# mixer.net
KiCad netlist of a schematic drawn in EAGLE
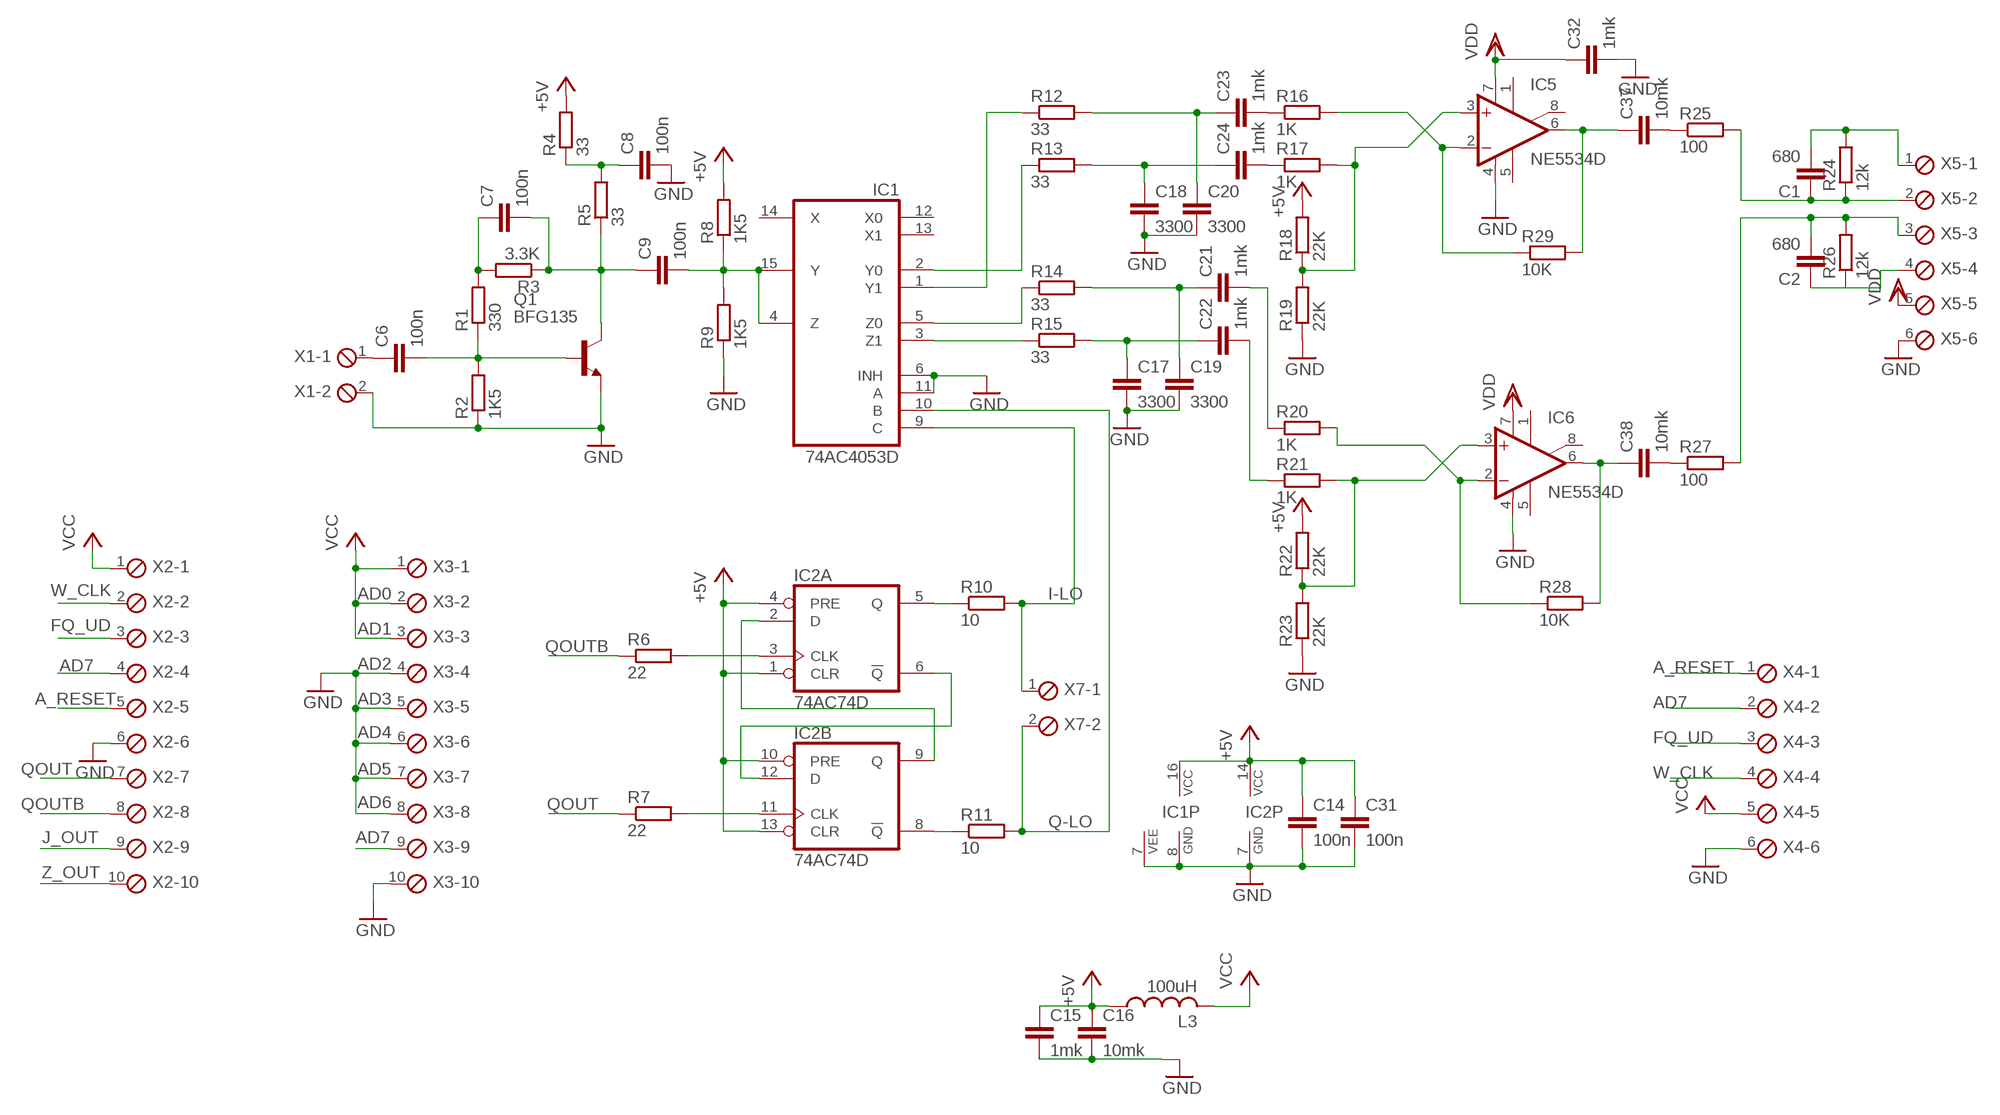
[diagram p0: schematic, sheet 1]

(export (version "E")
  (design (tool "Eeschema 10.0.6"))
  (components
    (comp (ref "C1")
      (value "680")
      (footprint "eagle-import:C0805")
      (libsource (lib "eagle-import") (part "C-EUC0805"))
    )
    (comp (ref "C2")
      (value "680")
      (footprint "eagle-import:C0805")
      (libsource (lib "eagle-import") (part "C-EUC0805"))
    )
    (comp (ref "C6")
      (value "100n")
      (footprint "eagle-import:C0603")
      (libsource (lib "eagle-import") (part "C-EUC0603"))
    )
    (comp (ref "C7")
      (value "100n")
      (footprint "eagle-import:C0603")
      (libsource (lib "eagle-import") (part "C-EUC0603"))
    )
    (comp (ref "C8")
      (value "100n")
      (footprint "eagle-import:C0603")
      (libsource (lib "eagle-import") (part "C-EUC0603"))
    )
    (comp (ref "C9")
      (value "100n")
      (footprint "eagle-import:C0603")
      (libsource (lib "eagle-import") (part "C-EUC0603"))
    )
    (comp (ref "C14")
      (value "100n")
      (footprint "eagle-import:C0603")
      (libsource (lib "eagle-import") (part "C-EUC0603"))
    )
    (comp (ref "C15")
      (value "1mk")
      (footprint "eagle-import:C0603")
      (libsource (lib "eagle-import") (part "C-EUC0603"))
    )
    (comp (ref "C16")
      (value "10mk")
      (footprint "eagle-import:C0805")
      (libsource (lib "eagle-import") (part "C-EUC0805"))
    )
    (comp (ref "C17")
      (value "3300")
      (footprint "eagle-import:C0805")
      (libsource (lib "eagle-import") (part "C-EUC0805"))
    )
    (comp (ref "C18")
      (value "3300")
      (footprint "eagle-import:C0805")
      (libsource (lib "eagle-import") (part "C-EUC0805"))
    )
    (comp (ref "C19")
      (value "3300")
      (footprint "eagle-import:C0805")
      (libsource (lib "eagle-import") (part "C-EUC0805"))
    )
    (comp (ref "C20")
      (value "3300")
      (footprint "eagle-import:C0805")
      (libsource (lib "eagle-import") (part "C-EUC0805"))
    )
    (comp (ref "C21")
      (value "1mk")
      (footprint "eagle-import:C0603")
      (libsource (lib "eagle-import") (part "C-EUC0603"))
    )
    (comp (ref "C22")
      (value "1mk")
      (footprint "eagle-import:C0603")
      (libsource (lib "eagle-import") (part "C-EUC0603"))
    )
    (comp (ref "C23")
      (value "1mk")
      (footprint "eagle-import:C0603")
      (libsource (lib "eagle-import") (part "C-EUC0603"))
    )
    (comp (ref "C24")
      (value "1mk")
      (footprint "eagle-import:C0603")
      (libsource (lib "eagle-import") (part "C-EUC0603"))
    )
    (comp (ref "C31")
      (value "100n")
      (footprint "eagle-import:C0603")
      (libsource (lib "eagle-import") (part "C-EUC0603"))
    )
    (comp (ref "C32")
      (value "1mk")
      (footprint "eagle-import:C0603")
      (libsource (lib "eagle-import") (part "C-EUC0603"))
    )
    (comp (ref "C37")
      (value "10mk")
      (footprint "eagle-import:C0805")
      (libsource (lib "eagle-import") (part "C-EUC0805"))
    )
    (comp (ref "C38")
      (value "10mk")
      (footprint "eagle-import:C0805")
      (libsource (lib "eagle-import") (part "C-EUC0805"))
    )
    (comp (ref "IC1")
      (value "74AC4053D")
      (footprint "eagle-import:SO16")
      (libsource (lib "eagle-import") (part "4053D"))
    )
    (comp (ref "IC2")
      (value "74AC74D")
      (footprint "eagle-import:SO14")
      (libsource (lib "eagle-import") (part "7474DAC"))
    )
    (comp (ref "IC5")
      (value "NE5534D")
      (footprint "eagle-import:SO08")
      (libsource (lib "eagle-import") (part "NE5534D"))
    )
    (comp (ref "IC6")
      (value "NE5534D")
      (footprint "eagle-import:SO08")
      (libsource (lib "eagle-import") (part "NE5534D"))
    )
    (comp (ref "L3")
      (value "100uH")
      (footprint "eagle-import:0207_12")
      (libsource (lib "eagle-import") (part "L-US0207/12"))
    )
    (comp (ref "Q1")
      (value "BFG135")
      (footprint "eagle-import:SOT223")
      (libsource (lib "eagle-import") (part "BFG135"))
    )
    (comp (ref "R1")
      (value "330")
      (footprint "eagle-import:R0603")
      (libsource (lib "eagle-import") (part "R-EU_R0603"))
    )
    (comp (ref "R2")
      (value "1K5")
      (footprint "eagle-import:R0603")
      (libsource (lib "eagle-import") (part "R-EU_R0603"))
    )
    (comp (ref "R3")
      (value "3.3K")
      (footprint "eagle-import:R0603")
      (libsource (lib "eagle-import") (part "R-EU_R0603"))
    )
    (comp (ref "R4")
      (value "33")
      (footprint "eagle-import:R0603")
      (libsource (lib "eagle-import") (part "R-EU_R0603"))
    )
    (comp (ref "R5")
      (value "33")
      (footprint "eagle-import:R0603")
      (libsource (lib "eagle-import") (part "R-EU_R0603"))
    )
    (comp (ref "R6")
      (value "22")
      (footprint "eagle-import:R0603")
      (libsource (lib "eagle-import") (part "R-EU_R0603"))
    )
    (comp (ref "R7")
      (value "22")
      (footprint "eagle-import:R0603")
      (libsource (lib "eagle-import") (part "R-EU_R0603"))
    )
    (comp (ref "R8")
      (value "1K5")
      (footprint "eagle-import:R0603")
      (libsource (lib "eagle-import") (part "R-EU_R0603"))
    )
    (comp (ref "R9")
      (value "1K5")
      (footprint "eagle-import:R0603")
      (libsource (lib "eagle-import") (part "R-EU_R0603"))
    )
    (comp (ref "R10")
      (value "10")
      (footprint "eagle-import:R0603")
      (libsource (lib "eagle-import") (part "R-EU_R0603"))
    )
    (comp (ref "R11")
      (value "10")
      (footprint "eagle-import:R0603")
      (libsource (lib "eagle-import") (part "R-EU_R0603"))
    )
    (comp (ref "R12")
      (value "33")
      (footprint "eagle-import:R0603")
      (libsource (lib "eagle-import") (part "R-EU_R0603"))
    )
    (comp (ref "R13")
      (value "33")
      (footprint "eagle-import:R0603")
      (libsource (lib "eagle-import") (part "R-EU_R0603"))
    )
    (comp (ref "R14")
      (value "33")
      (footprint "eagle-import:R0603")
      (libsource (lib "eagle-import") (part "R-EU_R0603"))
    )
    (comp (ref "R15")
      (value "33")
      (footprint "eagle-import:R0603")
      (libsource (lib "eagle-import") (part "R-EU_R0603"))
    )
    (comp (ref "R16")
      (value "1K")
      (footprint "eagle-import:R0603")
      (libsource (lib "eagle-import") (part "R-EU_R0603"))
    )
    (comp (ref "R17")
      (value "1K")
      (footprint "eagle-import:R0603")
      (libsource (lib "eagle-import") (part "R-EU_R0603"))
    )
    (comp (ref "R18")
      (value "22K")
      (footprint "eagle-import:R0603")
      (libsource (lib "eagle-import") (part "R-EU_R0603"))
    )
    (comp (ref "R19")
      (value "22K")
      (footprint "eagle-import:R0603")
      (libsource (lib "eagle-import") (part "R-EU_R0603"))
    )
    (comp (ref "R20")
      (value "1K")
      (footprint "eagle-import:R0603")
      (libsource (lib "eagle-import") (part "R-EU_R0603"))
    )
    (comp (ref "R21")
      (value "1K")
      (footprint "eagle-import:R0603")
      (libsource (lib "eagle-import") (part "R-EU_R0603"))
    )
    (comp (ref "R22")
      (value "22K")
      (footprint "eagle-import:R0603")
      (libsource (lib "eagle-import") (part "R-EU_R0603"))
    )
    (comp (ref "R23")
      (value "22K")
      (footprint "eagle-import:R0603")
      (libsource (lib "eagle-import") (part "R-EU_R0603"))
    )
    (comp (ref "R24")
      (value "12k")
      (footprint "eagle-import:R0603")
      (libsource (lib "eagle-import") (part "R-EU_R0603"))
    )
    (comp (ref "R25")
      (value "100")
      (footprint "eagle-import:R0603")
      (libsource (lib "eagle-import") (part "R-EU_R0603"))
    )
    (comp (ref "R26")
      (value "12k")
      (footprint "eagle-import:R0603")
      (libsource (lib "eagle-import") (part "R-EU_R0603"))
    )
    (comp (ref "R27")
      (value "100")
      (footprint "eagle-import:R0603")
      (libsource (lib "eagle-import") (part "R-EU_R0603"))
    )
    (comp (ref "R28")
      (value "10K")
      (footprint "eagle-import:R0603")
      (libsource (lib "eagle-import") (part "R-EU_R0603"))
    )
    (comp (ref "R29")
      (value "10K")
      (footprint "eagle-import:R0603")
      (libsource (lib "eagle-import") (part "R-EU_R0603"))
    )
    (comp (ref "X1")
      (value "MPT2")
      (footprint "eagle-import:2POL254")
      (libsource (lib "eagle-import") (part "MPT2"))
    )
    (comp (ref "X2")
      (value "MPT10")
      (footprint "eagle-import:10POL254")
      (libsource (lib "eagle-import") (part "MPT10"))
    )
    (comp (ref "X3")
      (value "MPT10")
      (footprint "eagle-import:10POL254")
      (libsource (lib "eagle-import") (part "MPT10"))
    )
    (comp (ref "X4")
      (value "MPT6")
      (footprint "eagle-import:6POL254")
      (libsource (lib "eagle-import") (part "MPT6"))
    )
    (comp (ref "X5")
      (value "MPT6")
      (footprint "eagle-import:6POL254")
      (libsource (lib "eagle-import") (part "MPT6"))
    )
    (comp (ref "X7")
      (value "MPT2")
      (footprint "eagle-import:2POL254")
      (libsource (lib "eagle-import") (part "MPT2"))
    )
  )
  (nets
    (net (code "1") (name "+5V") (class "Default")
      (node (ref "C14") (pin "1") (pinfunction "1_1") (pintype "passive"))
      (node (ref "C15") (pin "1") (pinfunction "1_1") (pintype "passive"))
      (node (ref "C16") (pin "1") (pinfunction "1_1") (pintype "passive"))
      (node (ref "C31") (pin "1") (pinfunction "1_1") (pintype "passive"))
      (node (ref "IC1") (pin "16") (pinfunction "VCC_16") (pintype "power_in"))
      (node (ref "IC2") (pin "1") (pinfunction "CLR_1") (pintype "input"))
      (node (ref "IC2") (pin "10") (pinfunction "PRE_10") (pintype "input"))
      (node (ref "IC2") (pin "13") (pinfunction "CLR_13") (pintype "input"))
      (node (ref "IC2") (pin "14") (pinfunction "VCC_14") (pintype "power_in"))
      (node (ref "IC2") (pin "4") (pinfunction "PRE_4") (pintype "input"))
      (node (ref "L3") (pin "1") (pinfunction "1_1") (pintype "passive"))
      (node (ref "R18") (pin "2") (pinfunction "2_2") (pintype "passive"))
      (node (ref "R22") (pin "2") (pinfunction "2_2") (pintype "passive"))
      (node (ref "R4") (pin "2") (pinfunction "2_2") (pintype "passive"))
      (node (ref "R8") (pin "2") (pinfunction "2_2") (pintype "passive"))
    )
    (net (code "2") (name "/AD7") (class "Default")
      (node (ref "X2") (pin "4") (pinfunction "1_4") (pintype "passive"))
      (node (ref "X4") (pin "2") (pinfunction "1_2") (pintype "passive"))
    )
    (net (code "3") (name "/A_RESET") (class "Default")
      (node (ref "X2") (pin "5") (pinfunction "1_5") (pintype "passive"))
      (node (ref "X4") (pin "1") (pinfunction "1_1") (pintype "passive"))
    )
    (net (code "4") (name "/FQ_UD") (class "Default")
      (node (ref "X2") (pin "3") (pinfunction "1_3") (pintype "passive"))
      (node (ref "X4") (pin "3") (pinfunction "1_3") (pintype "passive"))
    )
    (net (code "5") (name "/I-LO") (class "Default")
      (node (ref "IC1") (pin "9") (pinfunction "C_9") (pintype "input"))
      (node (ref "R10") (pin "2") (pinfunction "2_2") (pintype "passive"))
      (node (ref "X7") (pin "1") (pinfunction "1_1") (pintype "passive"))
    )
    (net (code "6") (name "/J_OUT") (class "Default")
      (node (ref "X2") (pin "9") (pinfunction "1_9") (pintype "passive"))
    )
    (net (code "7") (name "/Q-LO") (class "Default")
      (node (ref "IC1") (pin "10") (pinfunction "B_10") (pintype "input"))
      (node (ref "R11") (pin "2") (pinfunction "2_2") (pintype "passive"))
      (node (ref "X7") (pin "2") (pinfunction "1_2") (pintype "passive"))
    )
    (net (code "8") (name "/QOUT") (class "Default")
      (node (ref "R7") (pin "1") (pinfunction "1_1") (pintype "passive"))
      (node (ref "X2") (pin "7") (pinfunction "1_7") (pintype "passive"))
    )
    (net (code "9") (name "/QOUTB") (class "Default")
      (node (ref "R6") (pin "1") (pinfunction "1_1") (pintype "passive"))
      (node (ref "X2") (pin "8") (pinfunction "1_8") (pintype "passive"))
    )
    (net (code "10") (name "/W_CLK") (class "Default")
      (node (ref "X2") (pin "2") (pinfunction "1_2") (pintype "passive"))
      (node (ref "X4") (pin "4") (pinfunction "1_4") (pintype "passive"))
    )
    (net (code "11") (name "/Z_OUT") (class "Default")
      (node (ref "X2") (pin "10") (pinfunction "1_10") (pintype "passive"))
    )
    (net (code "12") (name "GND") (class "Default")
      (node (ref "C14") (pin "2") (pinfunction "2_2") (pintype "passive"))
      (node (ref "C15") (pin "2") (pinfunction "2_2") (pintype "passive"))
      (node (ref "C16") (pin "2") (pinfunction "2_2") (pintype "passive"))
      (node (ref "C17") (pin "2") (pinfunction "2_2") (pintype "passive"))
      (node (ref "C18") (pin "2") (pinfunction "2_2") (pintype "passive"))
      (node (ref "C19") (pin "2") (pinfunction "2_2") (pintype "passive"))
      (node (ref "C20") (pin "2") (pinfunction "2_2") (pintype "passive"))
      (node (ref "C31") (pin "2") (pinfunction "2_2") (pintype "passive"))
      (node (ref "C32") (pin "2") (pinfunction "2_2") (pintype "passive"))
      (node (ref "C8") (pin "2") (pinfunction "2_2") (pintype "passive"))
      (node (ref "IC1") (pin "11") (pinfunction "A_11") (pintype "input"))
      (node (ref "IC1") (pin "6") (pinfunction "INH_6") (pintype "input"))
      (node (ref "IC1") (pin "7") (pinfunction "VEE_7") (pintype "power_in"))
      (node (ref "IC1") (pin "8") (pinfunction "GND_8") (pintype "power_in"))
      (node (ref "IC2") (pin "7") (pinfunction "GND_7") (pintype "power_in"))
      (node (ref "IC5") (pin "4") (pinfunction "V-_4") (pintype "power_in"))
      (node (ref "IC6") (pin "4") (pinfunction "V-_4") (pintype "power_in"))
      (node (ref "Q1") (pin "1") (pinfunction "E_1") (pintype "passive"))
      (node (ref "Q1") (pin "3") (pinfunction "E_3") (pintype "passive"))
      (node (ref "R19") (pin "1") (pinfunction "1_1") (pintype "passive"))
      (node (ref "R2") (pin "1") (pinfunction "1_1") (pintype "passive"))
      (node (ref "R23") (pin "1") (pinfunction "1_1") (pintype "passive"))
      (node (ref "R9") (pin "1") (pinfunction "1_1") (pintype "passive"))
      (node (ref "X1") (pin "2") (pinfunction "1_2") (pintype "passive"))
      (node (ref "X2") (pin "6") (pinfunction "1_6") (pintype "passive"))
      (node (ref "X3") (pin "10") (pinfunction "1_10") (pintype "passive"))
      (node (ref "X3") (pin "4") (pinfunction "1_4") (pintype "passive"))
      (node (ref "X3") (pin "5") (pinfunction "1_5") (pintype "passive"))
      (node (ref "X3") (pin "6") (pinfunction "1_6") (pintype "passive"))
      (node (ref "X3") (pin "7") (pinfunction "1_7") (pintype "passive"))
      (node (ref "X3") (pin "8") (pinfunction "1_8") (pintype "passive"))
      (node (ref "X4") (pin "6") (pinfunction "1_6") (pintype "passive"))
      (node (ref "X5") (pin "6") (pinfunction "1_6") (pintype "passive"))
    )
    (net (code "13") (name "Net-(C1-Pad2)") (class "Default")
      (node (ref "C1") (pin "2") (pinfunction "2_2") (pintype "passive"))
      (node (ref "R24") (pin "2") (pinfunction "2_2") (pintype "passive"))
      (node (ref "X5") (pin "1") (pinfunction "1_1") (pintype "passive"))
    )
    (net (code "14") (name "Net-(C6-Pad1)") (class "Default")
      (node (ref "C6") (pin "1") (pinfunction "1_1") (pintype "passive"))
      (node (ref "X1") (pin "1") (pinfunction "1_1") (pintype "passive"))
    )
    (net (code "15") (name "Net-(C7-Pad1)") (class "Default")
      (node (ref "C7") (pin "1") (pinfunction "1_1") (pintype "passive"))
      (node (ref "R1") (pin "2") (pinfunction "2_2") (pintype "passive"))
      (node (ref "R3") (pin "2") (pinfunction "2_2") (pintype "passive"))
    )
    (net (code "16") (name "Net-(C8-Pad1)") (class "Default")
      (node (ref "C8") (pin "1") (pinfunction "1_1") (pintype "passive"))
      (node (ref "R4") (pin "1") (pinfunction "1_1") (pintype "passive"))
      (node (ref "R5") (pin "2") (pinfunction "2_2") (pintype "passive"))
    )
    (net (code "17") (name "Net-(C17-Pad1)") (class "Default")
      (node (ref "C17") (pin "1") (pinfunction "1_1") (pintype "passive"))
      (node (ref "C22") (pin "1") (pinfunction "1_1") (pintype "passive"))
      (node (ref "R15") (pin "2") (pinfunction "2_2") (pintype "passive"))
    )
    (net (code "18") (name "Net-(C18-Pad1)") (class "Default")
      (node (ref "C18") (pin "1") (pinfunction "1_1") (pintype "passive"))
      (node (ref "C24") (pin "1") (pinfunction "1_1") (pintype "passive"))
      (node (ref "R13") (pin "2") (pinfunction "2_2") (pintype "passive"))
    )
    (net (code "19") (name "Net-(C19-Pad1)") (class "Default")
      (node (ref "C19") (pin "1") (pinfunction "1_1") (pintype "passive"))
      (node (ref "C21") (pin "1") (pinfunction "1_1") (pintype "passive"))
      (node (ref "R14") (pin "2") (pinfunction "2_2") (pintype "passive"))
    )
    (net (code "20") (name "Net-(C20-Pad1)") (class "Default")
      (node (ref "C20") (pin "1") (pinfunction "1_1") (pintype "passive"))
      (node (ref "C23") (pin "1") (pinfunction "1_1") (pintype "passive"))
      (node (ref "R12") (pin "2") (pinfunction "2_2") (pintype "passive"))
    )
    (net (code "21") (name "Net-(C21-Pad2)") (class "Default")
      (node (ref "C21") (pin "2") (pinfunction "2_2") (pintype "passive"))
      (node (ref "R20") (pin "1") (pinfunction "1_1") (pintype "passive"))
    )
    (net (code "22") (name "Net-(C22-Pad2)") (class "Default")
      (node (ref "C22") (pin "2") (pinfunction "2_2") (pintype "passive"))
      (node (ref "R21") (pin "1") (pinfunction "1_1") (pintype "passive"))
    )
    (net (code "23") (name "Net-(C23-Pad2)") (class "Default")
      (node (ref "C23") (pin "2") (pinfunction "2_2") (pintype "passive"))
      (node (ref "R16") (pin "1") (pinfunction "1_1") (pintype "passive"))
    )
    (net (code "24") (name "Net-(C24-Pad2)") (class "Default")
      (node (ref "C24") (pin "2") (pinfunction "2_2") (pintype "passive"))
      (node (ref "R17") (pin "1") (pinfunction "1_1") (pintype "passive"))
    )
    (net (code "25") (name "Net-(C37-Pad2)") (class "Default")
      (node (ref "C37") (pin "2") (pinfunction "2_2") (pintype "passive"))
      (node (ref "R25") (pin "1") (pinfunction "1_1") (pintype "passive"))
    )
    (net (code "26") (name "Net-(C38-Pad2)") (class "Default")
      (node (ref "C38") (pin "2") (pinfunction "2_2") (pintype "passive"))
      (node (ref "R27") (pin "1") (pinfunction "1_1") (pintype "passive"))
    )
    (net (code "27") (name "Net-(IC1A-Y)") (class "Default")
      (node (ref "C9") (pin "2") (pinfunction "2_2") (pintype "passive"))
      (node (ref "IC1") (pin "15") (pinfunction "Y_15") (pintype "bidirectional"))
      (node (ref "IC1") (pin "4") (pinfunction "Z_4") (pintype "bidirectional"))
      (node (ref "R8") (pin "1") (pinfunction "1_1") (pintype "passive"))
      (node (ref "R9") (pin "2") (pinfunction "2_2") (pintype "passive"))
    )
    (net (code "28") (name "Net-(IC1A-Y0)") (class "Default")
      (node (ref "IC1") (pin "2") (pinfunction "Y0_2") (pintype "bidirectional"))
      (node (ref "R13") (pin "1") (pinfunction "1_1") (pintype "passive"))
    )
    (net (code "29") (name "Net-(IC1A-Y1)") (class "Default")
      (node (ref "IC1") (pin "1") (pinfunction "Y1_1") (pintype "bidirectional"))
      (node (ref "R12") (pin "1") (pinfunction "1_1") (pintype "passive"))
    )
    (net (code "30") (name "Net-(IC1A-Z0)") (class "Default")
      (node (ref "IC1") (pin "5") (pinfunction "Z0_5") (pintype "bidirectional"))
      (node (ref "R14") (pin "1") (pinfunction "1_1") (pintype "passive"))
    )
    (net (code "31") (name "Net-(IC1A-Z1)") (class "Default")
      (node (ref "IC1") (pin "3") (pinfunction "Z1_3") (pintype "bidirectional"))
      (node (ref "R15") (pin "1") (pinfunction "1_1") (pintype "passive"))
    )
    (net (code "32") (name "Net-(IC2A-CLK)") (class "Default")
      (node (ref "IC2") (pin "3") (pinfunction "CLK_3") (pintype "input"))
      (node (ref "R6") (pin "2") (pinfunction "2_2") (pintype "passive"))
    )
    (net (code "33") (name "Net-(IC2A-D)") (class "Default")
      (node (ref "IC2") (pin "2") (pinfunction "D_2") (pintype "input"))
      (node (ref "IC2") (pin "9") (pinfunction "Q_9") (pintype "output"))
    )
    (net (code "34") (name "Net-(IC2A-Q)") (class "Default")
      (node (ref "IC2") (pin "5") (pinfunction "Q_5") (pintype "output"))
      (node (ref "R10") (pin "1") (pinfunction "1_1") (pintype "passive"))
    )
    (net (code "35") (name "Net-(IC2A-~{Q})") (class "Default")
      (node (ref "IC2") (pin "12") (pinfunction "D_12") (pintype "input"))
      (node (ref "IC2") (pin "6") (pinfunction "~{Q}_6") (pintype "output"))
    )
    (net (code "36") (name "Net-(IC2B-CLK)") (class "Default")
      (node (ref "IC2") (pin "11") (pinfunction "CLK_11") (pintype "input"))
      (node (ref "R7") (pin "2") (pinfunction "2_2") (pintype "passive"))
    )
    (net (code "37") (name "Net-(IC2B-~{Q})") (class "Default")
      (node (ref "IC2") (pin "8") (pinfunction "~{Q}_8") (pintype "output"))
      (node (ref "R11") (pin "1") (pinfunction "1_1") (pintype "passive"))
    )
    (net (code "38") (name "Net-(IC5-+IN)") (class "Default")
      (node (ref "IC5") (pin "3") (pinfunction "+IN_3") (pintype "input"))
      (node (ref "R17") (pin "2") (pinfunction "2_2") (pintype "passive"))
      (node (ref "R18") (pin "1") (pinfunction "1_1") (pintype "passive"))
      (node (ref "R19") (pin "2") (pinfunction "2_2") (pintype "passive"))
    )
    (net (code "39") (name "Net-(IC5--IN)") (class "Default")
      (node (ref "IC5") (pin "2") (pinfunction "-IN_2") (pintype "input"))
      (node (ref "R16") (pin "2") (pinfunction "2_2") (pintype "passive"))
      (node (ref "R29") (pin "1") (pinfunction "1_1") (pintype "passive"))
    )
    (net (code "40") (name "Net-(IC5-OUT)") (class "Default")
      (node (ref "C37") (pin "1") (pinfunction "1_1") (pintype "passive"))
      (node (ref "IC5") (pin "6") (pinfunction "OUT_6") (pintype "output"))
      (node (ref "R29") (pin "2") (pinfunction "2_2") (pintype "passive"))
    )
    (net (code "41") (name "Net-(IC6-+IN)") (class "Default")
      (node (ref "IC6") (pin "3") (pinfunction "+IN_3") (pintype "input"))
      (node (ref "R21") (pin "2") (pinfunction "2_2") (pintype "passive"))
      (node (ref "R22") (pin "1") (pinfunction "1_1") (pintype "passive"))
      (node (ref "R23") (pin "2") (pinfunction "2_2") (pintype "passive"))
    )
    (net (code "42") (name "Net-(IC6--IN)") (class "Default")
      (node (ref "IC6") (pin "2") (pinfunction "-IN_2") (pintype "input"))
      (node (ref "R20") (pin "2") (pinfunction "2_2") (pintype "passive"))
      (node (ref "R28") (pin "1") (pinfunction "1_1") (pintype "passive"))
    )
    (net (code "43") (name "Net-(IC6-OUT)") (class "Default")
      (node (ref "C38") (pin "1") (pinfunction "1_1") (pintype "passive"))
      (node (ref "IC6") (pin "6") (pinfunction "OUT_6") (pintype "output"))
      (node (ref "R28") (pin "2") (pinfunction "2_2") (pintype "passive"))
    )
    (net (code "44") (name "Net-(Q1-B)") (class "Default")
      (node (ref "C6") (pin "2") (pinfunction "2_2") (pintype "passive"))
      (node (ref "Q1") (pin "2") (pinfunction "B_2") (pintype "passive"))
      (node (ref "R1") (pin "1") (pinfunction "1_1") (pintype "passive"))
      (node (ref "R2") (pin "2") (pinfunction "2_2") (pintype "passive"))
    )
    (net (code "45") (name "Net-(Q1-C)") (class "Default")
      (node (ref "C7") (pin "2") (pinfunction "2_2") (pintype "passive"))
      (node (ref "C9") (pin "1") (pinfunction "1_1") (pintype "passive"))
      (node (ref "Q1") (pin "4") (pinfunction "C_4") (pintype "passive"))
      (node (ref "R3") (pin "1") (pinfunction "1_1") (pintype "passive"))
      (node (ref "R5") (pin "1") (pinfunction "1_1") (pintype "passive"))
    )
    (net (code "46") (name "Net-(X5B-1)") (class "Default")
      (node (ref "C1") (pin "1") (pinfunction "1_1") (pintype "passive"))
      (node (ref "R24") (pin "1") (pinfunction "1_1") (pintype "passive"))
      (node (ref "R25") (pin "2") (pinfunction "2_2") (pintype "passive"))
      (node (ref "X5") (pin "2") (pinfunction "1_2") (pintype "passive"))
    )
    (net (code "47") (name "Net-(X5C-1)") (class "Default")
      (node (ref "C2") (pin "2") (pinfunction "2_2") (pintype "passive"))
      (node (ref "R26") (pin "2") (pinfunction "2_2") (pintype "passive"))
      (node (ref "R27") (pin "2") (pinfunction "2_2") (pintype "passive"))
      (node (ref "X5") (pin "3") (pinfunction "1_3") (pintype "passive"))
    )
    (net (code "48") (name "Net-(X5D-1)") (class "Default")
      (node (ref "C2") (pin "1") (pinfunction "1_1") (pintype "passive"))
      (node (ref "R26") (pin "1") (pinfunction "1_1") (pintype "passive"))
      (node (ref "X5") (pin "4") (pinfunction "1_4") (pintype "passive"))
    )
    (net (code "49") (name "VCC") (class "Default")
      (node (ref "L3") (pin "2") (pinfunction "2_2") (pintype "passive"))
      (node (ref "X2") (pin "1") (pinfunction "1_1") (pintype "passive"))
      (node (ref "X3") (pin "1") (pinfunction "1_1") (pintype "passive"))
      (node (ref "X3") (pin "2") (pinfunction "1_2") (pintype "passive"))
      (node (ref "X3") (pin "3") (pinfunction "1_3") (pintype "passive"))
      (node (ref "X4") (pin "5") (pinfunction "1_5") (pintype "passive"))
    )
    (net (code "50") (name "VDD") (class "Default")
      (node (ref "C32") (pin "1") (pinfunction "1_1") (pintype "passive"))
      (node (ref "IC5") (pin "7") (pinfunction "V+_7") (pintype "power_in"))
      (node (ref "IC6") (pin "7") (pinfunction "V+_7") (pintype "power_in"))
      (node (ref "X5") (pin "5") (pinfunction "1_5") (pintype "passive"))
    )
    (net (code "51") (name "unconnected-(IC1A-X-Pad14)") (class "Default")
      (node (ref "IC1") (pin "14") (pinfunction "X_14") (pintype "bidirectional"))
    )
    (net (code "52") (name "unconnected-(IC1A-X0-Pad12)") (class "Default")
      (node (ref "IC1") (pin "12") (pinfunction "X0_12") (pintype "bidirectional"))
    )
    (net (code "53") (name "unconnected-(IC1A-X1-Pad13)") (class "Default")
      (node (ref "IC1") (pin "13") (pinfunction "X1_13") (pintype "bidirectional"))
    )
    (net (code "54") (name "unconnected-(IC5-CMP-Pad5)") (class "Default")
      (node (ref "IC5") (pin "5") (pinfunction "CMP_5") (pintype "passive"))
    )
    (net (code "55") (name "unconnected-(IC5-ON-Pad1)") (class "Default")
      (node (ref "IC5") (pin "1") (pinfunction "ON_1") (pintype "passive"))
    )
    (net (code "56") (name "unconnected-(IC5-ON{slash}CMP-Pad8)") (class "Default")
      (node (ref "IC5") (pin "8") (pinfunction "ON/CMP_8") (pintype "passive"))
    )
    (net (code "57") (name "unconnected-(IC6-CMP-Pad5)") (class "Default")
      (node (ref "IC6") (pin "5") (pinfunction "CMP_5") (pintype "passive"))
    )
    (net (code "58") (name "unconnected-(IC6-ON-Pad1)") (class "Default")
      (node (ref "IC6") (pin "1") (pinfunction "ON_1") (pintype "passive"))
    )
    (net (code "59") (name "unconnected-(IC6-ON{slash}CMP-Pad8)") (class "Default")
      (node (ref "IC6") (pin "8") (pinfunction "ON/CMP_8") (pintype "passive"))
    )
    (net (code "60") (name "unconnected-(X3J-1-Pad9)") (class "Default")
      (node (ref "X3") (pin "9") (pinfunction "1_9") (pintype "passive"))
    )
  )
)
